# numitron-clock.net
KiCad netlist of a schematic drawn in EAGLE
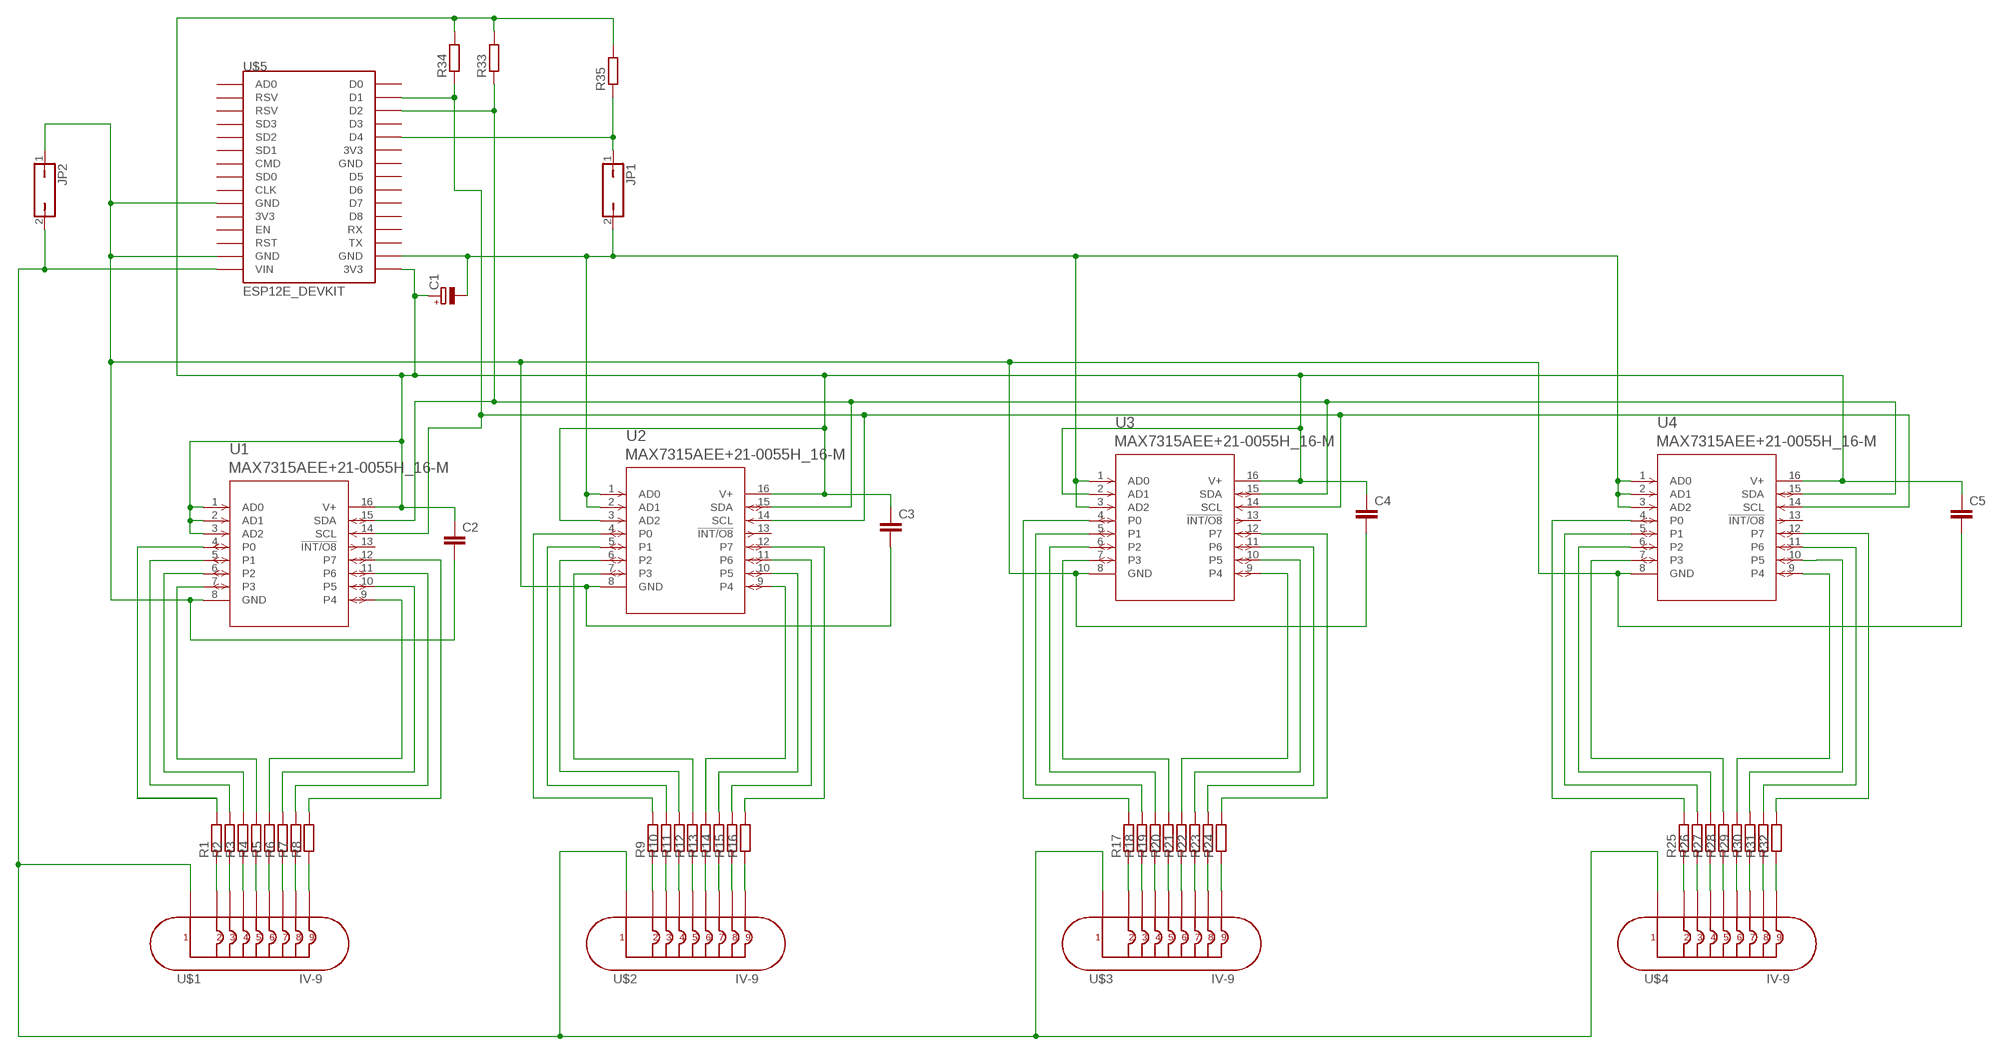
[diagram p0: schematic, sheet 1]

(export (version "E")
  (design (tool "Eeschema 10.0.6"))
  (components
    (comp (ref "C1")
      (value "CPOL-EUE2,5-6E")
      (footprint "eagle-import:E2,5-6E")
      (libsource (lib "eagle-import") (part "CPOL-EUE2,5-6E"))
    )
    (comp (ref "C2")
      (value "C-EUC0603")
      (footprint "eagle-import:C0603")
      (libsource (lib "eagle-import") (part "C-EUC0603"))
    )
    (comp (ref "C3")
      (value "C-EUC0603")
      (footprint "eagle-import:C0603")
      (libsource (lib "eagle-import") (part "C-EUC0603"))
    )
    (comp (ref "C4")
      (value "C-EUC0603")
      (footprint "eagle-import:C0603")
      (libsource (lib "eagle-import") (part "C-EUC0603"))
    )
    (comp (ref "C5")
      (value "C-EUC0603")
      (footprint "eagle-import:C0603")
      (libsource (lib "eagle-import") (part "C-EUC0603"))
    )
    (comp (ref "JP1")
      (value "JP1Q")
      (footprint "eagle-import:JP1")
      (libsource (lib "eagle-import") (part "JP1Q"))
    )
    (comp (ref "JP2")
      (value "JP1Q")
      (footprint "eagle-import:JP1")
      (libsource (lib "eagle-import") (part "JP1Q"))
    )
    (comp (ref "R1")
      (value "R-EU_R0603")
      (footprint "eagle-import:R0603")
      (libsource (lib "eagle-import") (part "R-EU_R0603"))
    )
    (comp (ref "R2")
      (value "R-EU_R0603")
      (footprint "eagle-import:R0603")
      (libsource (lib "eagle-import") (part "R-EU_R0603"))
    )
    (comp (ref "R3")
      (value "R-EU_R0603")
      (footprint "eagle-import:R0603")
      (libsource (lib "eagle-import") (part "R-EU_R0603"))
    )
    (comp (ref "R4")
      (value "R-EU_R0603")
      (footprint "eagle-import:R0603")
      (libsource (lib "eagle-import") (part "R-EU_R0603"))
    )
    (comp (ref "R5")
      (value "R-EU_R0603")
      (footprint "eagle-import:R0603")
      (libsource (lib "eagle-import") (part "R-EU_R0603"))
    )
    (comp (ref "R6")
      (value "R-EU_R0603")
      (footprint "eagle-import:R0603")
      (libsource (lib "eagle-import") (part "R-EU_R0603"))
    )
    (comp (ref "R7")
      (value "R-EU_R0603")
      (footprint "eagle-import:R0603")
      (libsource (lib "eagle-import") (part "R-EU_R0603"))
    )
    (comp (ref "R8")
      (value "R-EU_R0603")
      (footprint "eagle-import:R0603")
      (libsource (lib "eagle-import") (part "R-EU_R0603"))
    )
    (comp (ref "R9")
      (value "R-EU_R0603")
      (footprint "eagle-import:R0603")
      (libsource (lib "eagle-import") (part "R-EU_R0603"))
    )
    (comp (ref "R10")
      (value "R-EU_R0603")
      (footprint "eagle-import:R0603")
      (libsource (lib "eagle-import") (part "R-EU_R0603"))
    )
    (comp (ref "R11")
      (value "R-EU_R0603")
      (footprint "eagle-import:R0603")
      (libsource (lib "eagle-import") (part "R-EU_R0603"))
    )
    (comp (ref "R12")
      (value "R-EU_R0603")
      (footprint "eagle-import:R0603")
      (libsource (lib "eagle-import") (part "R-EU_R0603"))
    )
    (comp (ref "R13")
      (value "R-EU_R0603")
      (footprint "eagle-import:R0603")
      (libsource (lib "eagle-import") (part "R-EU_R0603"))
    )
    (comp (ref "R14")
      (value "R-EU_R0603")
      (footprint "eagle-import:R0603")
      (libsource (lib "eagle-import") (part "R-EU_R0603"))
    )
    (comp (ref "R15")
      (value "R-EU_R0603")
      (footprint "eagle-import:R0603")
      (libsource (lib "eagle-import") (part "R-EU_R0603"))
    )
    (comp (ref "R16")
      (value "R-EU_R0603")
      (footprint "eagle-import:R0603")
      (libsource (lib "eagle-import") (part "R-EU_R0603"))
    )
    (comp (ref "R17")
      (value "R-EU_R0603")
      (footprint "eagle-import:R0603")
      (libsource (lib "eagle-import") (part "R-EU_R0603"))
    )
    (comp (ref "R18")
      (value "R-EU_R0603")
      (footprint "eagle-import:R0603")
      (libsource (lib "eagle-import") (part "R-EU_R0603"))
    )
    (comp (ref "R19")
      (value "R-EU_R0603")
      (footprint "eagle-import:R0603")
      (libsource (lib "eagle-import") (part "R-EU_R0603"))
    )
    (comp (ref "R20")
      (value "R-EU_R0603")
      (footprint "eagle-import:R0603")
      (libsource (lib "eagle-import") (part "R-EU_R0603"))
    )
    (comp (ref "R21")
      (value "R-EU_R0603")
      (footprint "eagle-import:R0603")
      (libsource (lib "eagle-import") (part "R-EU_R0603"))
    )
    (comp (ref "R22")
      (value "R-EU_R0603")
      (footprint "eagle-import:R0603")
      (libsource (lib "eagle-import") (part "R-EU_R0603"))
    )
    (comp (ref "R23")
      (value "R-EU_R0603")
      (footprint "eagle-import:R0603")
      (libsource (lib "eagle-import") (part "R-EU_R0603"))
    )
    (comp (ref "R24")
      (value "R-EU_R0603")
      (footprint "eagle-import:R0603")
      (libsource (lib "eagle-import") (part "R-EU_R0603"))
    )
    (comp (ref "R25")
      (value "R-EU_R0603")
      (footprint "eagle-import:R0603")
      (libsource (lib "eagle-import") (part "R-EU_R0603"))
    )
    (comp (ref "R26")
      (value "R-EU_R0603")
      (footprint "eagle-import:R0603")
      (libsource (lib "eagle-import") (part "R-EU_R0603"))
    )
    (comp (ref "R27")
      (value "R-EU_R0603")
      (footprint "eagle-import:R0603")
      (libsource (lib "eagle-import") (part "R-EU_R0603"))
    )
    (comp (ref "R28")
      (value "R-EU_R0603")
      (footprint "eagle-import:R0603")
      (libsource (lib "eagle-import") (part "R-EU_R0603"))
    )
    (comp (ref "R29")
      (value "R-EU_R0603")
      (footprint "eagle-import:R0603")
      (libsource (lib "eagle-import") (part "R-EU_R0603"))
    )
    (comp (ref "R30")
      (value "R-EU_R0603")
      (footprint "eagle-import:R0603")
      (libsource (lib "eagle-import") (part "R-EU_R0603"))
    )
    (comp (ref "R31")
      (value "R-EU_R0603")
      (footprint "eagle-import:R0603")
      (libsource (lib "eagle-import") (part "R-EU_R0603"))
    )
    (comp (ref "R32")
      (value "R-EU_R0603")
      (footprint "eagle-import:R0603")
      (libsource (lib "eagle-import") (part "R-EU_R0603"))
    )
    (comp (ref "R33")
      (value "R-EU_R0603")
      (footprint "eagle-import:R0603")
      (libsource (lib "eagle-import") (part "R-EU_R0603"))
    )
    (comp (ref "R34")
      (value "R-EU_R0603")
      (footprint "eagle-import:R0603")
      (libsource (lib "eagle-import") (part "R-EU_R0603"))
    )
    (comp (ref "R35")
      (value "R-EU_R0603")
      (footprint "eagle-import:R0603")
      (libsource (lib "eagle-import") (part "R-EU_R0603"))
    )
    (comp (ref "U$1")
      (value "IV-9")
      (footprint "eagle-import:IV-9")
      (libsource (lib "eagle-import") (part "IV-9"))
    )
    (comp (ref "U$2")
      (value "IV-9")
      (footprint "eagle-import:IV-9")
      (libsource (lib "eagle-import") (part "IV-9"))
    )
    (comp (ref "U$3")
      (value "IV-9")
      (footprint "eagle-import:IV-9")
      (libsource (lib "eagle-import") (part "IV-9"))
    )
    (comp (ref "U$4")
      (value "IV-9")
      (footprint "eagle-import:IV-9")
      (libsource (lib "eagle-import") (part "IV-9"))
    )
    (comp (ref "U$5")
      (value "ESP12E_DEVKIT")
      (footprint "eagle-import:ESP12E_DEVKIT")
      (libsource (lib "eagle-import") (part "ESP12E_DEVKIT"))
    )
    (comp (ref "U1")
      (value "MAX7315AEE+21-0055H_16-M")
      (footprint "eagle-import:21-0055H_16-M")
      (fields
        (field (name "MANUFACTURER_PART_NUMBER") "MAX7315AEE+")
        (field (name "COPYRIGHT") "Copyright (C) 2024 Ultra Librarian. All rights reserved.")
      )
      (libsource (lib "eagle-import") (part "MAX7315AEE+21-0055H_16-M"))
    )
    (comp (ref "U2")
      (value "MAX7315AEE+21-0055H_16-M")
      (footprint "eagle-import:21-0055H_16-M")
      (fields
        (field (name "MANUFACTURER_PART_NUMBER") "MAX7315AEE+")
        (field (name "COPYRIGHT") "Copyright (C) 2024 Ultra Librarian. All rights reserved.")
      )
      (libsource (lib "eagle-import") (part "MAX7315AEE+21-0055H_16-M"))
    )
    (comp (ref "U3")
      (value "MAX7315AEE+21-0055H_16-M")
      (footprint "eagle-import:21-0055H_16-M")
      (fields
        (field (name "MANUFACTURER_PART_NUMBER") "MAX7315AEE+")
        (field (name "COPYRIGHT") "Copyright (C) 2024 Ultra Librarian. All rights reserved.")
      )
      (libsource (lib "eagle-import") (part "MAX7315AEE+21-0055H_16-M"))
    )
    (comp (ref "U4")
      (value "MAX7315AEE+21-0055H_16-M")
      (footprint "eagle-import:21-0055H_16-M")
      (fields
        (field (name "MANUFACTURER_PART_NUMBER") "MAX7315AEE+")
        (field (name "COPYRIGHT") "Copyright (C) 2024 Ultra Librarian. All rights reserved.")
      )
      (libsource (lib "eagle-import") (part "MAX7315AEE+21-0055H_16-M"))
    )
  )
  (nets
    (net (code "1") (name "Net-(JP1-Pad1)") (class "Default")
      (node (ref "JP1") (pin "1") (pinfunction "1_1") (pintype "passive"))
      (node (ref "R35") (pin "1") (pinfunction "1_1") (pintype "passive"))
      (node (ref "U$5") (pin "D4") (pinfunction "D4_D4") (pintype "bidirectional"))
    )
    (net (code "2") (name "Net-(JP2-Pad2)") (class "Default")
      (node (ref "JP2") (pin "2") (pinfunction "2_2") (pintype "passive"))
      (node (ref "U$1") (pin "1") (pinfunction "1_1") (pintype "bidirectional"))
      (node (ref "U$2") (pin "1") (pinfunction "1_1") (pintype "bidirectional"))
      (node (ref "U$3") (pin "1") (pinfunction "1_1") (pintype "bidirectional"))
      (node (ref "U$4") (pin "1") (pinfunction "1_1") (pintype "bidirectional"))
      (node (ref "U$5") (pin "VIN") (pinfunction "VIN_VIN") (pintype "bidirectional"))
    )
    (net (code "3") (name "Net-(R1-Pad1)") (class "Default")
      (node (ref "R1") (pin "1") (pinfunction "1_1") (pintype "passive"))
      (node (ref "U$1") (pin "2") (pinfunction "2_2") (pintype "bidirectional"))
    )
    (net (code "4") (name "Net-(R2-Pad1)") (class "Default")
      (node (ref "R2") (pin "1") (pinfunction "1_1") (pintype "passive"))
      (node (ref "U$1") (pin "3") (pinfunction "3_3") (pintype "bidirectional"))
    )
    (net (code "5") (name "Net-(R3-Pad1)") (class "Default")
      (node (ref "R3") (pin "1") (pinfunction "1_1") (pintype "passive"))
      (node (ref "U$1") (pin "4") (pinfunction "4_4") (pintype "bidirectional"))
    )
    (net (code "6") (name "Net-(R4-Pad1)") (class "Default")
      (node (ref "R4") (pin "1") (pinfunction "1_1") (pintype "passive"))
      (node (ref "U$1") (pin "5") (pinfunction "5_5") (pintype "bidirectional"))
    )
    (net (code "7") (name "Net-(R5-Pad1)") (class "Default")
      (node (ref "R5") (pin "1") (pinfunction "1_1") (pintype "passive"))
      (node (ref "U$1") (pin "6") (pinfunction "6_6") (pintype "bidirectional"))
    )
    (net (code "8") (name "Net-(R6-Pad1)") (class "Default")
      (node (ref "R6") (pin "1") (pinfunction "1_1") (pintype "passive"))
      (node (ref "U$1") (pin "7") (pinfunction "7_7") (pintype "bidirectional"))
    )
    (net (code "9") (name "Net-(R7-Pad1)") (class "Default")
      (node (ref "R7") (pin "1") (pinfunction "1_1") (pintype "passive"))
      (node (ref "U$1") (pin "8") (pinfunction "8_8") (pintype "bidirectional"))
    )
    (net (code "10") (name "Net-(R8-Pad1)") (class "Default")
      (node (ref "R8") (pin "1") (pinfunction "1_1") (pintype "passive"))
      (node (ref "U$1") (pin "9") (pinfunction "9_9") (pintype "bidirectional"))
    )
    (net (code "11") (name "Net-(R9-Pad1)") (class "Default")
      (node (ref "R9") (pin "1") (pinfunction "1_1") (pintype "passive"))
      (node (ref "U$2") (pin "2") (pinfunction "2_2") (pintype "bidirectional"))
    )
    (net (code "12") (name "Net-(R10-Pad1)") (class "Default")
      (node (ref "R10") (pin "1") (pinfunction "1_1") (pintype "passive"))
      (node (ref "U$2") (pin "3") (pinfunction "3_3") (pintype "bidirectional"))
    )
    (net (code "13") (name "Net-(R11-Pad1)") (class "Default")
      (node (ref "R11") (pin "1") (pinfunction "1_1") (pintype "passive"))
      (node (ref "U$2") (pin "4") (pinfunction "4_4") (pintype "bidirectional"))
    )
    (net (code "14") (name "Net-(R12-Pad1)") (class "Default")
      (node (ref "R12") (pin "1") (pinfunction "1_1") (pintype "passive"))
      (node (ref "U$2") (pin "5") (pinfunction "5_5") (pintype "bidirectional"))
    )
    (net (code "15") (name "Net-(R13-Pad1)") (class "Default")
      (node (ref "R13") (pin "1") (pinfunction "1_1") (pintype "passive"))
      (node (ref "U$2") (pin "6") (pinfunction "6_6") (pintype "bidirectional"))
    )
    (net (code "16") (name "Net-(R14-Pad1)") (class "Default")
      (node (ref "R14") (pin "1") (pinfunction "1_1") (pintype "passive"))
      (node (ref "U$2") (pin "7") (pinfunction "7_7") (pintype "bidirectional"))
    )
    (net (code "17") (name "Net-(R15-Pad1)") (class "Default")
      (node (ref "R15") (pin "1") (pinfunction "1_1") (pintype "passive"))
      (node (ref "U$2") (pin "8") (pinfunction "8_8") (pintype "bidirectional"))
    )
    (net (code "18") (name "Net-(R16-Pad1)") (class "Default")
      (node (ref "R16") (pin "1") (pinfunction "1_1") (pintype "passive"))
      (node (ref "U$2") (pin "9") (pinfunction "9_9") (pintype "bidirectional"))
    )
    (net (code "19") (name "Net-(R17-Pad1)") (class "Default")
      (node (ref "R17") (pin "1") (pinfunction "1_1") (pintype "passive"))
      (node (ref "U$3") (pin "2") (pinfunction "2_2") (pintype "bidirectional"))
    )
    (net (code "20") (name "Net-(R18-Pad1)") (class "Default")
      (node (ref "R18") (pin "1") (pinfunction "1_1") (pintype "passive"))
      (node (ref "U$3") (pin "3") (pinfunction "3_3") (pintype "bidirectional"))
    )
    (net (code "21") (name "Net-(R19-Pad1)") (class "Default")
      (node (ref "R19") (pin "1") (pinfunction "1_1") (pintype "passive"))
      (node (ref "U$3") (pin "4") (pinfunction "4_4") (pintype "bidirectional"))
    )
    (net (code "22") (name "Net-(R20-Pad1)") (class "Default")
      (node (ref "R20") (pin "1") (pinfunction "1_1") (pintype "passive"))
      (node (ref "U$3") (pin "5") (pinfunction "5_5") (pintype "bidirectional"))
    )
    (net (code "23") (name "Net-(R21-Pad1)") (class "Default")
      (node (ref "R21") (pin "1") (pinfunction "1_1") (pintype "passive"))
      (node (ref "U$3") (pin "6") (pinfunction "6_6") (pintype "bidirectional"))
    )
    (net (code "24") (name "Net-(R22-Pad1)") (class "Default")
      (node (ref "R22") (pin "1") (pinfunction "1_1") (pintype "passive"))
      (node (ref "U$3") (pin "7") (pinfunction "7_7") (pintype "bidirectional"))
    )
    (net (code "25") (name "Net-(R23-Pad1)") (class "Default")
      (node (ref "R23") (pin "1") (pinfunction "1_1") (pintype "passive"))
      (node (ref "U$3") (pin "8") (pinfunction "8_8") (pintype "bidirectional"))
    )
    (net (code "26") (name "Net-(R24-Pad1)") (class "Default")
      (node (ref "R24") (pin "1") (pinfunction "1_1") (pintype "passive"))
      (node (ref "U$3") (pin "9") (pinfunction "9_9") (pintype "bidirectional"))
    )
    (net (code "27") (name "Net-(R25-Pad1)") (class "Default")
      (node (ref "R25") (pin "1") (pinfunction "1_1") (pintype "passive"))
      (node (ref "U$4") (pin "2") (pinfunction "2_2") (pintype "bidirectional"))
    )
    (net (code "28") (name "Net-(R26-Pad1)") (class "Default")
      (node (ref "R26") (pin "1") (pinfunction "1_1") (pintype "passive"))
      (node (ref "U$4") (pin "3") (pinfunction "3_3") (pintype "bidirectional"))
    )
    (net (code "29") (name "Net-(R27-Pad1)") (class "Default")
      (node (ref "R27") (pin "1") (pinfunction "1_1") (pintype "passive"))
      (node (ref "U$4") (pin "4") (pinfunction "4_4") (pintype "bidirectional"))
    )
    (net (code "30") (name "Net-(R28-Pad1)") (class "Default")
      (node (ref "R28") (pin "1") (pinfunction "1_1") (pintype "passive"))
      (node (ref "U$4") (pin "5") (pinfunction "5_5") (pintype "bidirectional"))
    )
    (net (code "31") (name "Net-(R29-Pad1)") (class "Default")
      (node (ref "R29") (pin "1") (pinfunction "1_1") (pintype "passive"))
      (node (ref "U$4") (pin "6") (pinfunction "6_6") (pintype "bidirectional"))
    )
    (net (code "32") (name "Net-(R30-Pad1)") (class "Default")
      (node (ref "R30") (pin "1") (pinfunction "1_1") (pintype "passive"))
      (node (ref "U$4") (pin "7") (pinfunction "7_7") (pintype "bidirectional"))
    )
    (net (code "33") (name "Net-(R31-Pad1)") (class "Default")
      (node (ref "R31") (pin "1") (pinfunction "1_1") (pintype "passive"))
      (node (ref "U$4") (pin "8") (pinfunction "8_8") (pintype "bidirectional"))
    )
    (net (code "34") (name "Net-(R32-Pad1)") (class "Default")
      (node (ref "R32") (pin "1") (pinfunction "1_1") (pintype "passive"))
      (node (ref "U$4") (pin "9") (pinfunction "9_9") (pintype "bidirectional"))
    )
    (net (code "35") (name "Net-(U1-AD0)") (class "Default")
      (node (ref "C1") (pin "+") (pinfunction "+_+") (pintype "passive"))
      (node (ref "C2") (pin "1") (pinfunction "1_1") (pintype "passive"))
      (node (ref "C3") (pin "1") (pinfunction "1_1") (pintype "passive"))
      (node (ref "C4") (pin "1") (pinfunction "1_1") (pintype "passive"))
      (node (ref "C5") (pin "1") (pinfunction "1_1") (pintype "passive"))
      (node (ref "R33") (pin "2") (pinfunction "2_2") (pintype "passive"))
      (node (ref "R34") (pin "2") (pinfunction "2_2") (pintype "passive"))
      (node (ref "R35") (pin "2") (pinfunction "2_2") (pintype "passive"))
      (node (ref "U$5") (pin "3V3@2") (pinfunction "3V3_3V3@2") (pintype "bidirectional"))
      (node (ref "U1") (pin "1") (pinfunction "AD0_1") (pintype "input"))
      (node (ref "U1") (pin "16") (pinfunction "V+_16") (pintype "power_in"))
      (node (ref "U1") (pin "2") (pinfunction "AD1_2") (pintype "input"))
      (node (ref "U1") (pin "3") (pinfunction "AD2_3") (pintype "input"))
      (node (ref "U2") (pin "16") (pinfunction "V+_16") (pintype "power_in"))
      (node (ref "U2") (pin "3") (pinfunction "AD2_3") (pintype "input"))
      (node (ref "U3") (pin "16") (pinfunction "V+_16") (pintype "power_in"))
      (node (ref "U3") (pin "2") (pinfunction "AD1_2") (pintype "input"))
      (node (ref "U4") (pin "16") (pinfunction "V+_16") (pintype "power_in"))
    )
    (net (code "36") (name "Net-(U1-GND)") (class "Default")
      (node (ref "C2") (pin "2") (pinfunction "2_2") (pintype "passive"))
      (node (ref "C3") (pin "2") (pinfunction "2_2") (pintype "passive"))
      (node (ref "C4") (pin "2") (pinfunction "2_2") (pintype "passive"))
      (node (ref "C5") (pin "2") (pinfunction "2_2") (pintype "passive"))
      (node (ref "JP2") (pin "1") (pinfunction "1_1") (pintype "passive"))
      (node (ref "U$5") (pin "GND@0") (pinfunction "GND_GND@0") (pintype "bidirectional"))
      (node (ref "U$5") (pin "GND@1") (pinfunction "GND_GND@1") (pintype "bidirectional"))
      (node (ref "U1") (pin "8") (pinfunction "GND_8") (pintype "power_in"))
      (node (ref "U2") (pin "8") (pinfunction "GND_8") (pintype "power_in"))
      (node (ref "U3") (pin "8") (pinfunction "GND_8") (pintype "power_in"))
      (node (ref "U4") (pin "8") (pinfunction "GND_8") (pintype "power_in"))
    )
    (net (code "37") (name "Net-(U1-P0)") (class "Default")
      (node (ref "R1") (pin "2") (pinfunction "2_2") (pintype "passive"))
      (node (ref "U1") (pin "4") (pinfunction "P0_4") (pintype "bidirectional"))
    )
    (net (code "38") (name "Net-(U1-P1)") (class "Default")
      (node (ref "R2") (pin "2") (pinfunction "2_2") (pintype "passive"))
      (node (ref "U1") (pin "5") (pinfunction "P1_5") (pintype "bidirectional"))
    )
    (net (code "39") (name "Net-(U1-P2)") (class "Default")
      (node (ref "R3") (pin "2") (pinfunction "2_2") (pintype "passive"))
      (node (ref "U1") (pin "6") (pinfunction "P2_6") (pintype "bidirectional"))
    )
    (net (code "40") (name "Net-(U1-P3)") (class "Default")
      (node (ref "R4") (pin "2") (pinfunction "2_2") (pintype "passive"))
      (node (ref "U1") (pin "7") (pinfunction "P3_7") (pintype "bidirectional"))
    )
    (net (code "41") (name "Net-(U1-P4)") (class "Default")
      (node (ref "R5") (pin "2") (pinfunction "2_2") (pintype "passive"))
      (node (ref "U1") (pin "9") (pinfunction "P4_9") (pintype "bidirectional"))
    )
    (net (code "42") (name "Net-(U1-P5)") (class "Default")
      (node (ref "R6") (pin "2") (pinfunction "2_2") (pintype "passive"))
      (node (ref "U1") (pin "10") (pinfunction "P5_10") (pintype "bidirectional"))
    )
    (net (code "43") (name "Net-(U1-P6)") (class "Default")
      (node (ref "R7") (pin "2") (pinfunction "2_2") (pintype "passive"))
      (node (ref "U1") (pin "11") (pinfunction "P6_11") (pintype "bidirectional"))
    )
    (net (code "44") (name "Net-(U1-P7)") (class "Default")
      (node (ref "R8") (pin "2") (pinfunction "2_2") (pintype "passive"))
      (node (ref "U1") (pin "12") (pinfunction "P7_12") (pintype "bidirectional"))
    )
    (net (code "45") (name "Net-(U1-SCL)") (class "Default")
      (node (ref "R34") (pin "1") (pinfunction "1_1") (pintype "passive"))
      (node (ref "U$5") (pin "D1") (pinfunction "D1_D1") (pintype "bidirectional"))
      (node (ref "U1") (pin "14") (pinfunction "SCL_14") (pintype "input"))
      (node (ref "U2") (pin "14") (pinfunction "SCL_14") (pintype "input"))
      (node (ref "U3") (pin "14") (pinfunction "SCL_14") (pintype "input"))
      (node (ref "U4") (pin "14") (pinfunction "SCL_14") (pintype "input"))
    )
    (net (code "46") (name "Net-(U1-SDA)") (class "Default")
      (node (ref "R33") (pin "1") (pinfunction "1_1") (pintype "passive"))
      (node (ref "U$5") (pin "D2") (pinfunction "D2_D2") (pintype "bidirectional"))
      (node (ref "U1") (pin "15") (pinfunction "SDA_15") (pintype "bidirectional"))
      (node (ref "U2") (pin "15") (pinfunction "SDA_15") (pintype "bidirectional"))
      (node (ref "U3") (pin "15") (pinfunction "SDA_15") (pintype "bidirectional"))
      (node (ref "U4") (pin "15") (pinfunction "SDA_15") (pintype "bidirectional"))
    )
    (net (code "47") (name "Net-(U2-AD0)") (class "Default")
      (node (ref "C1") (pin "-") (pinfunction "-_-") (pintype "passive"))
      (node (ref "JP1") (pin "2") (pinfunction "2_2") (pintype "passive"))
      (node (ref "U$5") (pin "GND@3") (pinfunction "GND_GND@3") (pintype "bidirectional"))
      (node (ref "U2") (pin "1") (pinfunction "AD0_1") (pintype "input"))
      (node (ref "U2") (pin "2") (pinfunction "AD1_2") (pintype "input"))
      (node (ref "U3") (pin "1") (pinfunction "AD0_1") (pintype "input"))
      (node (ref "U3") (pin "3") (pinfunction "AD2_3") (pintype "input"))
      (node (ref "U4") (pin "1") (pinfunction "AD0_1") (pintype "input"))
      (node (ref "U4") (pin "2") (pinfunction "AD1_2") (pintype "input"))
      (node (ref "U4") (pin "3") (pinfunction "AD2_3") (pintype "input"))
    )
    (net (code "48") (name "Net-(U2-P0)") (class "Default")
      (node (ref "R9") (pin "2") (pinfunction "2_2") (pintype "passive"))
      (node (ref "U2") (pin "4") (pinfunction "P0_4") (pintype "bidirectional"))
    )
    (net (code "49") (name "Net-(U2-P1)") (class "Default")
      (node (ref "R10") (pin "2") (pinfunction "2_2") (pintype "passive"))
      (node (ref "U2") (pin "5") (pinfunction "P1_5") (pintype "bidirectional"))
    )
    (net (code "50") (name "Net-(U2-P2)") (class "Default")
      (node (ref "R11") (pin "2") (pinfunction "2_2") (pintype "passive"))
      (node (ref "U2") (pin "6") (pinfunction "P2_6") (pintype "bidirectional"))
    )
    (net (code "51") (name "Net-(U2-P3)") (class "Default")
      (node (ref "R12") (pin "2") (pinfunction "2_2") (pintype "passive"))
      (node (ref "U2") (pin "7") (pinfunction "P3_7") (pintype "bidirectional"))
    )
    (net (code "52") (name "Net-(U2-P4)") (class "Default")
      (node (ref "R13") (pin "2") (pinfunction "2_2") (pintype "passive"))
      (node (ref "U2") (pin "9") (pinfunction "P4_9") (pintype "bidirectional"))
    )
    (net (code "53") (name "Net-(U2-P5)") (class "Default")
      (node (ref "R14") (pin "2") (pinfunction "2_2") (pintype "passive"))
      (node (ref "U2") (pin "10") (pinfunction "P5_10") (pintype "bidirectional"))
    )
    (net (code "54") (name "Net-(U2-P6)") (class "Default")
      (node (ref "R15") (pin "2") (pinfunction "2_2") (pintype "passive"))
      (node (ref "U2") (pin "11") (pinfunction "P6_11") (pintype "bidirectional"))
    )
    (net (code "55") (name "Net-(U2-P7)") (class "Default")
      (node (ref "R16") (pin "2") (pinfunction "2_2") (pintype "passive"))
      (node (ref "U2") (pin "12") (pinfunction "P7_12") (pintype "bidirectional"))
    )
    (net (code "56") (name "Net-(U3-P0)") (class "Default")
      (node (ref "R17") (pin "2") (pinfunction "2_2") (pintype "passive"))
      (node (ref "U3") (pin "4") (pinfunction "P0_4") (pintype "bidirectional"))
    )
    (net (code "57") (name "Net-(U3-P1)") (class "Default")
      (node (ref "R18") (pin "2") (pinfunction "2_2") (pintype "passive"))
      (node (ref "U3") (pin "5") (pinfunction "P1_5") (pintype "bidirectional"))
    )
    (net (code "58") (name "Net-(U3-P2)") (class "Default")
      (node (ref "R19") (pin "2") (pinfunction "2_2") (pintype "passive"))
      (node (ref "U3") (pin "6") (pinfunction "P2_6") (pintype "bidirectional"))
    )
    (net (code "59") (name "Net-(U3-P3)") (class "Default")
      (node (ref "R20") (pin "2") (pinfunction "2_2") (pintype "passive"))
      (node (ref "U3") (pin "7") (pinfunction "P3_7") (pintype "bidirectional"))
    )
    (net (code "60") (name "Net-(U3-P4)") (class "Default")
      (node (ref "R21") (pin "2") (pinfunction "2_2") (pintype "passive"))
      (node (ref "U3") (pin "9") (pinfunction "P4_9") (pintype "bidirectional"))
    )
    (net (code "61") (name "Net-(U3-P5)") (class "Default")
      (node (ref "R22") (pin "2") (pinfunction "2_2") (pintype "passive"))
      (node (ref "U3") (pin "10") (pinfunction "P5_10") (pintype "bidirectional"))
    )
    (net (code "62") (name "Net-(U3-P6)") (class "Default")
      (node (ref "R23") (pin "2") (pinfunction "2_2") (pintype "passive"))
      (node (ref "U3") (pin "11") (pinfunction "P6_11") (pintype "bidirectional"))
    )
    (net (code "63") (name "Net-(U3-P7)") (class "Default")
      (node (ref "R24") (pin "2") (pinfunction "2_2") (pintype "passive"))
      (node (ref "U3") (pin "12") (pinfunction "P7_12") (pintype "bidirectional"))
    )
    (net (code "64") (name "Net-(U4-P0)") (class "Default")
      (node (ref "R25") (pin "2") (pinfunction "2_2") (pintype "passive"))
      (node (ref "U4") (pin "4") (pinfunction "P0_4") (pintype "bidirectional"))
    )
    (net (code "65") (name "Net-(U4-P1)") (class "Default")
      (node (ref "R26") (pin "2") (pinfunction "2_2") (pintype "passive"))
      (node (ref "U4") (pin "5") (pinfunction "P1_5") (pintype "bidirectional"))
    )
    (net (code "66") (name "Net-(U4-P2)") (class "Default")
      (node (ref "R27") (pin "2") (pinfunction "2_2") (pintype "passive"))
      (node (ref "U4") (pin "6") (pinfunction "P2_6") (pintype "bidirectional"))
    )
    (net (code "67") (name "Net-(U4-P3)") (class "Default")
      (node (ref "R28") (pin "2") (pinfunction "2_2") (pintype "passive"))
      (node (ref "U4") (pin "7") (pinfunction "P3_7") (pintype "bidirectional"))
    )
    (net (code "68") (name "Net-(U4-P4)") (class "Default")
      (node (ref "R29") (pin "2") (pinfunction "2_2") (pintype "passive"))
      (node (ref "U4") (pin "9") (pinfunction "P4_9") (pintype "bidirectional"))
    )
    (net (code "69") (name "Net-(U4-P5)") (class "Default")
      (node (ref "R30") (pin "2") (pinfunction "2_2") (pintype "passive"))
      (node (ref "U4") (pin "10") (pinfunction "P5_10") (pintype "bidirectional"))
    )
    (net (code "70") (name "Net-(U4-P6)") (class "Default")
      (node (ref "R31") (pin "2") (pinfunction "2_2") (pintype "passive"))
      (node (ref "U4") (pin "11") (pinfunction "P6_11") (pintype "bidirectional"))
    )
    (net (code "71") (name "Net-(U4-P7)") (class "Default")
      (node (ref "R32") (pin "2") (pinfunction "2_2") (pintype "passive"))
      (node (ref "U4") (pin "12") (pinfunction "P7_12") (pintype "bidirectional"))
    )
    (net (code "72") (name "unconnected-(U$5-3V3-Pad3V3@0)") (class "Default")
      (node (ref "U$5") (pin "3V3@0") (pinfunction "3V3_3V3@0") (pintype "bidirectional"))
    )
    (net (code "73") (name "unconnected-(U$5-3V3-Pad3V3@1)") (class "Default")
      (node (ref "U$5") (pin "3V3@1") (pinfunction "3V3_3V3@1") (pintype "bidirectional"))
    )
    (net (code "74") (name "unconnected-(U$5-GND-PadGND@2)") (class "Default")
      (node (ref "U$5") (pin "GND@2") (pinfunction "GND_GND@2") (pintype "bidirectional"))
    )
    (net (code "75") (name "unconnected-(U$5-PadAD0)") (class "Default")
      (node (ref "U$5") (pin "AD0") (pinfunction "AD0_AD0") (pintype "bidirectional"))
    )
    (net (code "76") (name "unconnected-(U$5-PadCLK)") (class "Default")
      (node (ref "U$5") (pin "CLK") (pinfunction "CLK_CLK") (pintype "bidirectional"))
    )
    (net (code "77") (name "unconnected-(U$5-PadCMD)") (class "Default")
      (node (ref "U$5") (pin "CMD") (pinfunction "CMD_CMD") (pintype "bidirectional"))
    )
    (net (code "78") (name "unconnected-(U$5-PadD0)") (class "Default")
      (node (ref "U$5") (pin "D0") (pinfunction "D0_D0") (pintype "bidirectional"))
    )
    (net (code "79") (name "unconnected-(U$5-PadD3)") (class "Default")
      (node (ref "U$5") (pin "D3") (pinfunction "D3_D3") (pintype "bidirectional"))
    )
    (net (code "80") (name "unconnected-(U$5-PadD5)") (class "Default")
      (node (ref "U$5") (pin "D5") (pinfunction "D5_D5") (pintype "bidirectional"))
    )
    (net (code "81") (name "unconnected-(U$5-PadD6)") (class "Default")
      (node (ref "U$5") (pin "D6") (pinfunction "D6_D6") (pintype "bidirectional"))
    )
    (net (code "82") (name "unconnected-(U$5-PadD7)") (class "Default")
      (node (ref "U$5") (pin "D7") (pinfunction "D7_D7") (pintype "bidirectional"))
    )
    (net (code "83") (name "unconnected-(U$5-PadD8)") (class "Default")
      (node (ref "U$5") (pin "D8") (pinfunction "D8_D8") (pintype "bidirectional"))
    )
    (net (code "84") (name "unconnected-(U$5-PadEN)") (class "Default")
      (node (ref "U$5") (pin "EN") (pinfunction "EN_EN") (pintype "bidirectional"))
    )
    (net (code "85") (name "unconnected-(U$5-PadRST)") (class "Default")
      (node (ref "U$5") (pin "RST") (pinfunction "RST_RST") (pintype "bidirectional"))
    )
    (net (code "86") (name "unconnected-(U$5-PadRX)") (class "Default")
      (node (ref "U$5") (pin "RX") (pinfunction "RX_RX") (pintype "bidirectional"))
    )
    (net (code "87") (name "unconnected-(U$5-PadSD0)") (class "Default")
      (node (ref "U$5") (pin "SD0") (pinfunction "SD0_SD0") (pintype "bidirectional"))
    )
    (net (code "88") (name "unconnected-(U$5-PadSD1)") (class "Default")
      (node (ref "U$5") (pin "SD1") (pinfunction "SD1_SD1") (pintype "bidirectional"))
    )
    (net (code "89") (name "unconnected-(U$5-PadSD2)") (class "Default")
      (node (ref "U$5") (pin "SD2") (pinfunction "SD2_SD2") (pintype "bidirectional"))
    )
    (net (code "90") (name "unconnected-(U$5-PadSD3)") (class "Default")
      (node (ref "U$5") (pin "SD3") (pinfunction "SD3_SD3") (pintype "bidirectional"))
    )
    (net (code "91") (name "unconnected-(U$5-PadTX)") (class "Default")
      (node (ref "U$5") (pin "TX") (pinfunction "TX_TX") (pintype "bidirectional"))
    )
    (net (code "92") (name "unconnected-(U$5-RSV-PadRSV@0)") (class "Default")
      (node (ref "U$5") (pin "RSV@0") (pinfunction "RSV_RSV@0") (pintype "bidirectional"))
    )
    (net (code "93") (name "unconnected-(U$5-RSV-PadRSV@1)") (class "Default")
      (node (ref "U$5") (pin "RSV@1") (pinfunction "RSV_RSV@1") (pintype "bidirectional"))
    )
    (net (code "94") (name "unconnected-(U1-~{INT{slash}O8}-Pad13)") (class "Default")
      (node (ref "U1") (pin "13") (pinfunction "~{INT/O8}_13") (pintype "output"))
    )
    (net (code "95") (name "unconnected-(U2-~{INT{slash}O8}-Pad13)") (class "Default")
      (node (ref "U2") (pin "13") (pinfunction "~{INT/O8}_13") (pintype "output"))
    )
    (net (code "96") (name "unconnected-(U3-~{INT{slash}O8}-Pad13)") (class "Default")
      (node (ref "U3") (pin "13") (pinfunction "~{INT/O8}_13") (pintype "output"))
    )
    (net (code "97") (name "unconnected-(U4-~{INT{slash}O8}-Pad13)") (class "Default")
      (node (ref "U4") (pin "13") (pinfunction "~{INT/O8}_13") (pintype "output"))
    )
  )
)
